# TeensyTAF_4_Board_2_Small.net
KiCad netlist of a schematic drawn in EAGLE
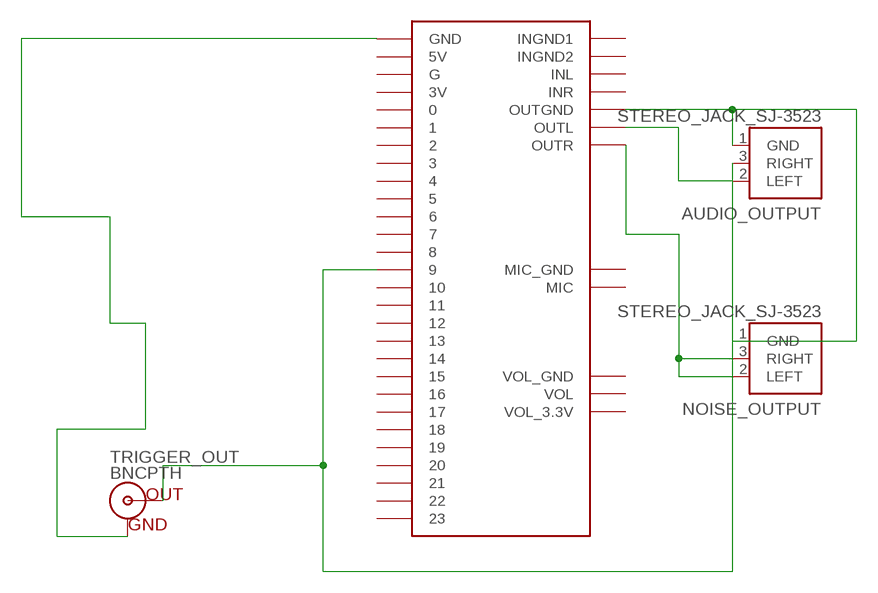
[diagram p0: schematic, sheet 1]

(export (version "E")
  (design (tool "Eeschema 10.0.6"))
  (components
    (comp (ref "AUDIO_OUTPUT")
      (value "STEREO_JACK_SJ-3523")
      (footprint "eagle-import:SJ-3523")
      (libsource (lib "eagle-import") (part "STEREO_JACK_SJ-3523"))
    )
    (comp (ref "NOISE_OUTPUT")
      (value "STEREO_JACK_SJ-3523")
      (footprint "eagle-import:SJ-3523")
      (libsource (lib "eagle-import") (part "STEREO_JACK_SJ-3523"))
    )
    (comp (ref "TRIGGER_OUT")
      (value "BNCPTH")
      (footprint "eagle-import:BNC")
      (libsource (lib "eagle-import") (part "BNCPTH"))
    )
    (comp (ref "U$3")
      (value "AUDIOSHIELD")
      (footprint "eagle-import:AUDIOSHIELD")
      (libsource (lib "eagle-import") (part "AUDIOSHIELD"))
    )
  )
  (nets
    (net (code "1") (name "Net-(AUDIO_OUTPUT-GND)") (class "Default")
      (node (ref "AUDIO_OUTPUT") (pin "1") (pinfunction "GND_1") (pintype "power_in"))
      (node (ref "NOISE_OUTPUT") (pin "1") (pinfunction "GND_1") (pintype "power_in"))
      (node (ref "U$3") (pin "OUTGND") (pinfunction "OUTGND_OUTGND") (pintype "bidirectional"))
    )
    (net (code "2") (name "Net-(AUDIO_OUTPUT-LEFT)") (class "Default")
      (node (ref "AUDIO_OUTPUT") (pin "2") (pinfunction "LEFT_2") (pintype "output"))
      (node (ref "U$3") (pin "OUTL") (pinfunction "OUTL_OUTL") (pintype "output"))
    )
    (net (code "3") (name "Net-(AUDIO_OUTPUT-RIGHT)") (class "Default")
      (node (ref "AUDIO_OUTPUT") (pin "3") (pinfunction "RIGHT_3") (pintype "output"))
      (node (ref "TRIGGER_OUT") (pin "S") (pinfunction "OUT_S") (pintype "bidirectional"))
      (node (ref "U$3") (pin "9") (pinfunction "9_9") (pintype "bidirectional"))
    )
    (net (code "4") (name "Net-(NOISE_OUTPUT-LEFT)") (class "Default")
      (node (ref "NOISE_OUTPUT") (pin "2") (pinfunction "LEFT_2") (pintype "output"))
      (node (ref "NOISE_OUTPUT") (pin "3") (pinfunction "RIGHT_3") (pintype "output"))
      (node (ref "U$3") (pin "OUTR") (pinfunction "OUTR_OUTR") (pintype "output"))
    )
    (net (code "5") (name "Net-(TRIGGER_OUT-PadGND)") (class "Default")
      (node (ref "TRIGGER_OUT") (pin "GND") (pinfunction "GND_GND") (pintype "bidirectional"))
      (node (ref "U$3") (pin "GND") (pinfunction "GND_GND") (pintype "bidirectional"))
    )
    (net (code "6") (name "unconnected-(U$3-MIC_GND-PadGND_MIC)") (class "Default")
      (node (ref "U$3") (pin "GND_MIC") (pinfunction "MIC_GND_GND_MIC") (pintype "bidirectional"))
    )
    (net (code "7") (name "unconnected-(U$3-Pad0)") (class "Default")
      (node (ref "U$3") (pin "0") (pinfunction "0_0") (pintype "bidirectional"))
    )
    (net (code "8") (name "unconnected-(U$3-Pad1)") (class "Default")
      (node (ref "U$3") (pin "1") (pinfunction "1_1") (pintype "bidirectional"))
    )
    (net (code "9") (name "unconnected-(U$3-Pad2)") (class "Default")
      (node (ref "U$3") (pin "2") (pinfunction "2_2") (pintype "bidirectional"))
    )
    (net (code "10") (name "unconnected-(U$3-Pad3)") (class "Default")
      (node (ref "U$3") (pin "3") (pinfunction "3_3") (pintype "bidirectional"))
    )
    (net (code "11") (name "unconnected-(U$3-Pad3V)") (class "Default")
      (node (ref "U$3") (pin "3V") (pinfunction "3V_3V") (pintype "bidirectional"))
    )
    (net (code "12") (name "unconnected-(U$3-Pad4)") (class "Default")
      (node (ref "U$3") (pin "4") (pinfunction "4_4") (pintype "bidirectional"))
    )
    (net (code "13") (name "unconnected-(U$3-Pad5)") (class "Default")
      (node (ref "U$3") (pin "5") (pinfunction "5_5") (pintype "bidirectional"))
    )
    (net (code "14") (name "unconnected-(U$3-Pad5V)") (class "Default")
      (node (ref "U$3") (pin "5V") (pinfunction "5V_5V") (pintype "bidirectional"))
    )
    (net (code "15") (name "unconnected-(U$3-Pad6)") (class "Default")
      (node (ref "U$3") (pin "6") (pinfunction "6_6") (pintype "bidirectional"))
    )
    (net (code "16") (name "unconnected-(U$3-Pad7)") (class "Default")
      (node (ref "U$3") (pin "7") (pinfunction "7_7") (pintype "bidirectional"))
    )
    (net (code "17") (name "unconnected-(U$3-Pad8)") (class "Default")
      (node (ref "U$3") (pin "8") (pinfunction "8_8") (pintype "bidirectional"))
    )
    (net (code "18") (name "unconnected-(U$3-Pad10)") (class "Default")
      (node (ref "U$3") (pin "10") (pinfunction "10_10") (pintype "bidirectional"))
    )
    (net (code "19") (name "unconnected-(U$3-Pad11)") (class "Default")
      (node (ref "U$3") (pin "11") (pinfunction "11_11") (pintype "bidirectional"))
    )
    (net (code "20") (name "unconnected-(U$3-Pad12)") (class "Default")
      (node (ref "U$3") (pin "12") (pinfunction "12_12") (pintype "bidirectional"))
    )
    (net (code "21") (name "unconnected-(U$3-Pad13)") (class "Default")
      (node (ref "U$3") (pin "13") (pinfunction "13_13") (pintype "bidirectional"))
    )
    (net (code "22") (name "unconnected-(U$3-Pad14)") (class "Default")
      (node (ref "U$3") (pin "14") (pinfunction "14_14") (pintype "bidirectional"))
    )
    (net (code "23") (name "unconnected-(U$3-Pad15)") (class "Default")
      (node (ref "U$3") (pin "15") (pinfunction "15_15") (pintype "bidirectional"))
    )
    (net (code "24") (name "unconnected-(U$3-Pad16)") (class "Default")
      (node (ref "U$3") (pin "16") (pinfunction "16_16") (pintype "bidirectional"))
    )
    (net (code "25") (name "unconnected-(U$3-Pad17)") (class "Default")
      (node (ref "U$3") (pin "17") (pinfunction "17_17") (pintype "bidirectional"))
    )
    (net (code "26") (name "unconnected-(U$3-Pad18)") (class "Default")
      (node (ref "U$3") (pin "18") (pinfunction "18_18") (pintype "bidirectional"))
    )
    (net (code "27") (name "unconnected-(U$3-Pad19)") (class "Default")
      (node (ref "U$3") (pin "19") (pinfunction "19_19") (pintype "bidirectional"))
    )
    (net (code "28") (name "unconnected-(U$3-Pad20)") (class "Default")
      (node (ref "U$3") (pin "20") (pinfunction "20_20") (pintype "bidirectional"))
    )
    (net (code "29") (name "unconnected-(U$3-Pad21)") (class "Default")
      (node (ref "U$3") (pin "21") (pinfunction "21_21") (pintype "bidirectional"))
    )
    (net (code "30") (name "unconnected-(U$3-Pad22)") (class "Default")
      (node (ref "U$3") (pin "22") (pinfunction "22_22") (pintype "bidirectional"))
    )
    (net (code "31") (name "unconnected-(U$3-Pad23)") (class "Default")
      (node (ref "U$3") (pin "23") (pinfunction "23_23") (pintype "bidirectional"))
    )
    (net (code "32") (name "unconnected-(U$3-PadG)") (class "Default")
      (node (ref "U$3") (pin "G") (pinfunction "G_G") (pintype "bidirectional"))
    )
    (net (code "33") (name "unconnected-(U$3-PadINGND1)") (class "Default")
      (node (ref "U$3") (pin "INGND1") (pinfunction "INGND1_INGND1") (pintype "bidirectional"))
    )
    (net (code "34") (name "unconnected-(U$3-PadINGND2)") (class "Default")
      (node (ref "U$3") (pin "INGND2") (pinfunction "INGND2_INGND2") (pintype "bidirectional"))
    )
    (net (code "35") (name "unconnected-(U$3-PadINL)") (class "Default")
      (node (ref "U$3") (pin "INL") (pinfunction "INL_INL") (pintype "input"))
    )
    (net (code "36") (name "unconnected-(U$3-PadINR)") (class "Default")
      (node (ref "U$3") (pin "INR") (pinfunction "INR_INR") (pintype "input"))
    )
    (net (code "37") (name "unconnected-(U$3-PadMIC)") (class "Default")
      (node (ref "U$3") (pin "MIC") (pinfunction "MIC_MIC") (pintype "input"))
    )
    (net (code "38") (name "unconnected-(U$3-PadVOL)") (class "Default")
      (node (ref "U$3") (pin "VOL") (pinfunction "VOL_VOL") (pintype "input"))
    )
    (net (code "39") (name "unconnected-(U$3-PadVOL_3.3V)") (class "Default")
      (node (ref "U$3") (pin "VOL_3.3V") (pinfunction "VOL_3.3V_VOL_3.3V") (pintype "bidirectional"))
    )
    (net (code "40") (name "unconnected-(U$3-PadVOL_GND)") (class "Default")
      (node (ref "U$3") (pin "VOL_GND") (pinfunction "VOL_GND_VOL_GND") (pintype "bidirectional"))
    )
  )
)
